# Aktivfilter.net
KiCad netlist of a schematic drawn in EAGLE
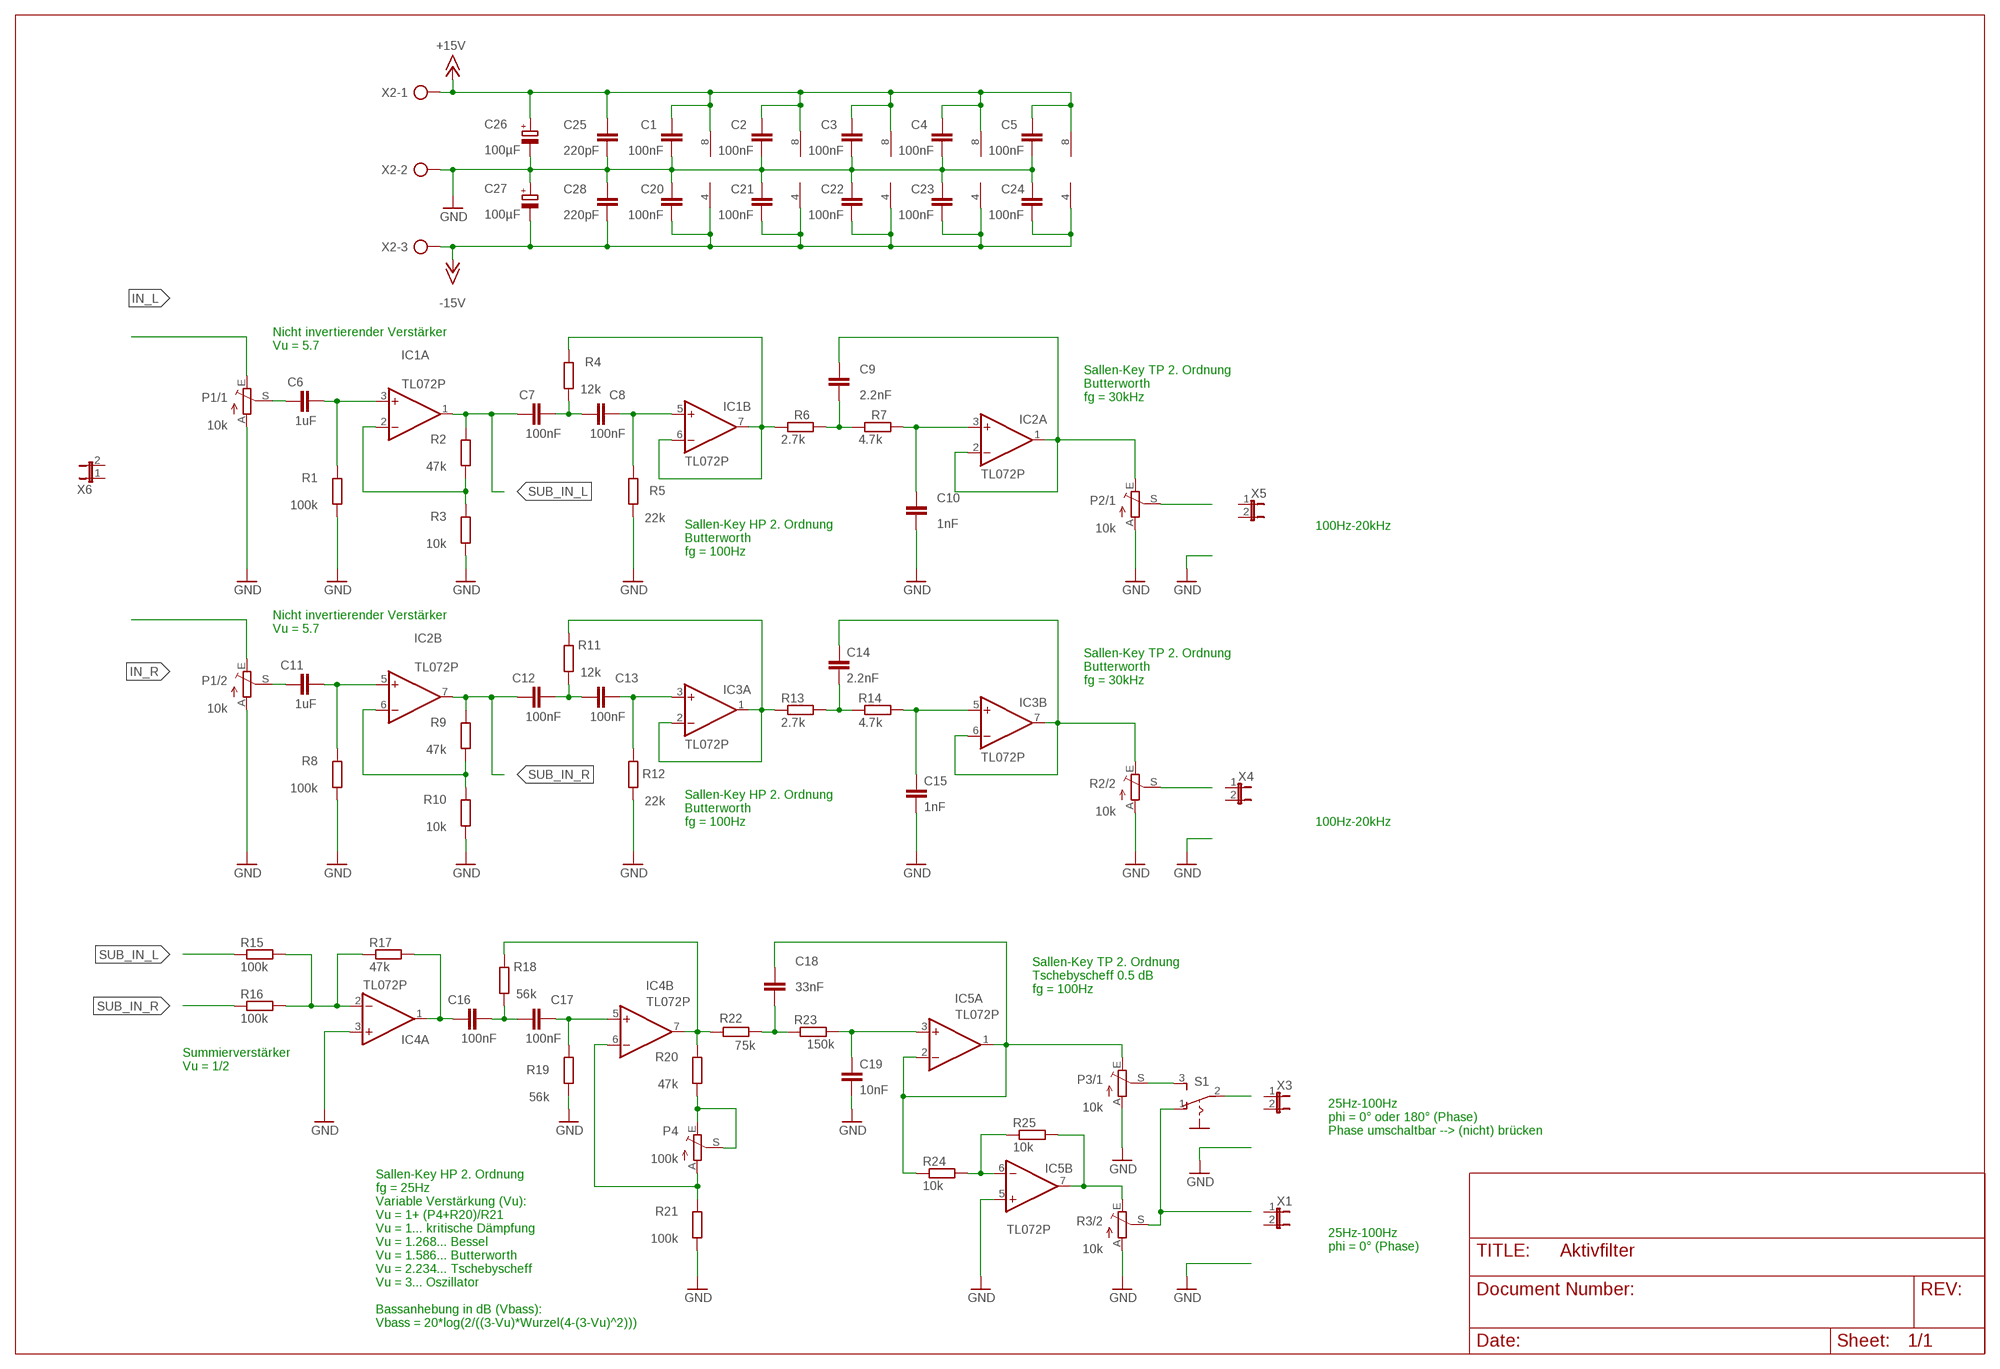
[diagram p0: schematic, sheet 1]

(export (version "E")
  (design (tool "Eeschema 10.0.6"))
  (components
    (comp (ref "C1")
      (value "100nF")
      (footprint "eagle-import:C025-025X050")
      (libsource (lib "eagle-import") (part "C-EU025-025X050"))
    )
    (comp (ref "C2")
      (value "100nF")
      (footprint "eagle-import:C025-025X050")
      (libsource (lib "eagle-import") (part "C-EU025-025X050"))
    )
    (comp (ref "C3")
      (value "100nF")
      (footprint "eagle-import:C025-025X050")
      (libsource (lib "eagle-import") (part "C-EU025-025X050"))
    )
    (comp (ref "C4")
      (value "100nF")
      (footprint "eagle-import:C025-025X050")
      (libsource (lib "eagle-import") (part "C-EU025-025X050"))
    )
    (comp (ref "C5")
      (value "100nF")
      (footprint "eagle-import:C025-025X050")
      (libsource (lib "eagle-import") (part "C-EU025-025X050"))
    )
    (comp (ref "C6")
      (value "1uF")
      (footprint "eagle-import:C025-025X050")
      (libsource (lib "eagle-import") (part "resistor_C-EU025-025X050"))
    )
    (comp (ref "C7")
      (value "100nF")
      (footprint "eagle-import:C025-025X050")
      (libsource (lib "eagle-import") (part "resistor_C-EU025-025X050"))
    )
    (comp (ref "C8")
      (value "100nF")
      (footprint "eagle-import:C025-025X050")
      (libsource (lib "eagle-import") (part "resistor_C-EU025-025X050"))
    )
    (comp (ref "C9")
      (value "2.2nF")
      (footprint "eagle-import:C025-025X050")
      (libsource (lib "eagle-import") (part "resistor_C-EU025-025X050"))
    )
    (comp (ref "C10")
      (value "1nF")
      (footprint "eagle-import:C025-025X050")
      (libsource (lib "eagle-import") (part "resistor_C-EU025-025X050"))
    )
    (comp (ref "C11")
      (value "1uF")
      (footprint "eagle-import:C025-025X050")
      (libsource (lib "eagle-import") (part "resistor_C-EU025-025X050"))
    )
    (comp (ref "C12")
      (value "100nF")
      (footprint "eagle-import:C025-025X050")
      (libsource (lib "eagle-import") (part "resistor_C-EU025-025X050"))
    )
    (comp (ref "C13")
      (value "100nF")
      (footprint "eagle-import:C025-025X050")
      (libsource (lib "eagle-import") (part "resistor_C-EU025-025X050"))
    )
    (comp (ref "C14")
      (value "2.2nF")
      (footprint "eagle-import:C025-025X050")
      (libsource (lib "eagle-import") (part "resistor_C-EU025-025X050"))
    )
    (comp (ref "C15")
      (value "1nF")
      (footprint "eagle-import:C025-025X050")
      (libsource (lib "eagle-import") (part "resistor_C-EU025-025X050"))
    )
    (comp (ref "C16")
      (value "100nF")
      (footprint "eagle-import:C050-025X075")
      (libsource (lib "eagle-import") (part "C-EU050-025X075"))
    )
    (comp (ref "C17")
      (value "100nF")
      (footprint "eagle-import:C025-025X050")
      (libsource (lib "eagle-import") (part "C-EU025-025X050"))
    )
    (comp (ref "C18")
      (value "33nF")
      (footprint "eagle-import:C025-025X050")
      (libsource (lib "eagle-import") (part "C-EU025-025X050"))
    )
    (comp (ref "C19")
      (value "10nF")
      (footprint "eagle-import:C025-025X050")
      (libsource (lib "eagle-import") (part "C-EU025-025X050"))
    )
    (comp (ref "C20")
      (value "100nF")
      (footprint "eagle-import:C025-025X050")
      (libsource (lib "eagle-import") (part "C-EU025-025X050"))
    )
    (comp (ref "C21")
      (value "100nF")
      (footprint "eagle-import:C025-025X050")
      (libsource (lib "eagle-import") (part "C-EU025-025X050"))
    )
    (comp (ref "C22")
      (value "100nF")
      (footprint "eagle-import:C025-025X050")
      (libsource (lib "eagle-import") (part "C-EU025-025X050"))
    )
    (comp (ref "C23")
      (value "100nF")
      (footprint "eagle-import:C025-025X050")
      (libsource (lib "eagle-import") (part "C-EU025-025X050"))
    )
    (comp (ref "C24")
      (value "100nF")
      (footprint "eagle-import:C025-025X050")
      (libsource (lib "eagle-import") (part "C-EU025-025X050"))
    )
    (comp (ref "C25")
      (value "220pF")
      (footprint "eagle-import:C025-025X050")
      (libsource (lib "eagle-import") (part "C-EU025-025X050"))
    )
    (comp (ref "C26")
      (value "100µF")
      (footprint "eagle-import:E2,5-6")
      (libsource (lib "eagle-import") (part "CPOL-EUE2.5-6"))
    )
    (comp (ref "C27")
      (value "100µF")
      (footprint "eagle-import:E2,5-6")
      (libsource (lib "eagle-import") (part "CPOL-EUE2.5-6"))
    )
    (comp (ref "C28")
      (value "220pF")
      (footprint "eagle-import:C025-025X050")
      (libsource (lib "eagle-import") (part "C-EU025-025X050"))
    )
    (comp (ref "IC1")
      (value "TL072P")
      (footprint "eagle-import:DIL08")
      (libsource (lib "eagle-import") (part "TL072P"))
    )
    (comp (ref "IC2")
      (value "TL072P")
      (footprint "eagle-import:DIL08")
      (libsource (lib "eagle-import") (part "TL072P"))
    )
    (comp (ref "IC3")
      (value "TL072P")
      (footprint "eagle-import:DIL08")
      (libsource (lib "eagle-import") (part "TL072P"))
    )
    (comp (ref "IC4")
      (value "TL072P")
      (footprint "eagle-import:DIL08")
      (libsource (lib "eagle-import") (part "TL072P"))
    )
    (comp (ref "IC5")
      (value "TL072P")
      (footprint "eagle-import:DIL08")
      (libsource (lib "eagle-import") (part "TL072P"))
    )
    (comp (ref "P1/1")
      (value "10k")
      (footprint "eagle-import:B64Y")
      (libsource (lib "eagle-import") (part "TRIM_EU-B64Y"))
    )
    (comp (ref "P1/2")
      (value "10k")
      (footprint "eagle-import:B64Y")
      (libsource (lib "eagle-import") (part "TRIM_EU-B64Y"))
    )
    (comp (ref "P2/1")
      (value "10k")
      (footprint "eagle-import:B64Y")
      (libsource (lib "eagle-import") (part "TRIM_EU-B64Y"))
    )
    (comp (ref "P3/1")
      (value "10k")
      (footprint "eagle-import:B64Y")
      (libsource (lib "eagle-import") (part "TRIM_EU-B64Y"))
    )
    (comp (ref "P4")
      (value "100k")
      (footprint "eagle-import:B64Y")
      (libsource (lib "eagle-import") (part "TRIM_EU-B64Y"))
    )
    (comp (ref "R1")
      (value "100k")
      (footprint "eagle-import:0207_10")
      (libsource (lib "eagle-import") (part "resistor_R-EU_0207/10"))
    )
    (comp (ref "R2")
      (value "47k")
      (footprint "eagle-import:0207_10")
      (libsource (lib "eagle-import") (part "resistor_R-EU_0207/10"))
    )
    (comp (ref "R2/2")
      (value "10k")
      (footprint "eagle-import:B64Y")
      (libsource (lib "eagle-import") (part "TRIM_EU-B64Y"))
    )
    (comp (ref "R3")
      (value "10k")
      (footprint "eagle-import:0207_10")
      (libsource (lib "eagle-import") (part "resistor_R-EU_0207/10"))
    )
    (comp (ref "R3/2")
      (value "10k")
      (footprint "eagle-import:B64Y")
      (libsource (lib "eagle-import") (part "TRIM_EU-B64Y"))
    )
    (comp (ref "R4")
      (value "12k")
      (footprint "eagle-import:0207_10")
      (libsource (lib "eagle-import") (part "resistor_R-EU_0207/10"))
    )
    (comp (ref "R5")
      (value "22k")
      (footprint "eagle-import:0207_10")
      (libsource (lib "eagle-import") (part "resistor_R-EU_0207/10"))
    )
    (comp (ref "R6")
      (value "2.7k")
      (footprint "eagle-import:0207_10")
      (libsource (lib "eagle-import") (part "resistor_R-EU_0207/10"))
    )
    (comp (ref "R7")
      (value "4.7k")
      (footprint "eagle-import:0207_10")
      (libsource (lib "eagle-import") (part "resistor_R-EU_0207/10"))
    )
    (comp (ref "R8")
      (value "100k")
      (footprint "eagle-import:0207_7")
      (libsource (lib "eagle-import") (part "R-EU_0207/7"))
    )
    (comp (ref "R9")
      (value "47k")
      (footprint "eagle-import:0207_7")
      (libsource (lib "eagle-import") (part "R-EU_0207/7"))
    )
    (comp (ref "R10")
      (value "10k")
      (footprint "eagle-import:0207_10")
      (libsource (lib "eagle-import") (part "resistor_R-EU_0207/10"))
    )
    (comp (ref "R11")
      (value "12k")
      (footprint "eagle-import:0207_10")
      (libsource (lib "eagle-import") (part "resistor_R-EU_0207/10"))
    )
    (comp (ref "R12")
      (value "22k")
      (footprint "eagle-import:0207_10")
      (libsource (lib "eagle-import") (part "resistor_R-EU_0207/10"))
    )
    (comp (ref "R13")
      (value "2.7k")
      (footprint "eagle-import:0207_10")
      (libsource (lib "eagle-import") (part "resistor_R-EU_0207/10"))
    )
    (comp (ref "R14")
      (value "4.7k")
      (footprint "eagle-import:0207_10")
      (libsource (lib "eagle-import") (part "resistor_R-EU_0207/10"))
    )
    (comp (ref "R15")
      (value "100k")
      (footprint "eagle-import:0207_10")
      (libsource (lib "eagle-import") (part "R-EU_0207/10"))
    )
    (comp (ref "R16")
      (value "100k")
      (footprint "eagle-import:0207_10")
      (libsource (lib "eagle-import") (part "R-EU_0207/10"))
    )
    (comp (ref "R17")
      (value "47k")
      (footprint "eagle-import:0207_10")
      (libsource (lib "eagle-import") (part "R-EU_0207/10"))
    )
    (comp (ref "R18")
      (value "56k")
      (footprint "eagle-import:0207_10")
      (libsource (lib "eagle-import") (part "R-EU_0207/10"))
    )
    (comp (ref "R19")
      (value "56k")
      (footprint "eagle-import:0207_7")
      (libsource (lib "eagle-import") (part "R-EU_0207/7"))
    )
    (comp (ref "R20")
      (value "47k")
      (footprint "eagle-import:0207_10")
      (libsource (lib "eagle-import") (part "R-EU_0207/10"))
    )
    (comp (ref "R21")
      (value "100k")
      (footprint "eagle-import:0207_10")
      (libsource (lib "eagle-import") (part "R-EU_0207/10"))
    )
    (comp (ref "R22")
      (value "75k")
      (footprint "eagle-import:0207_7")
      (libsource (lib "eagle-import") (part "R-EU_0207/7"))
    )
    (comp (ref "R23")
      (value "150k")
      (footprint "eagle-import:0207_10")
      (libsource (lib "eagle-import") (part "R-EU_0207/10"))
    )
    (comp (ref "R24")
      (value "10k")
      (footprint "eagle-import:0207_10")
      (libsource (lib "eagle-import") (part "R-EU_0207/10"))
    )
    (comp (ref "R25")
      (value "10k")
      (footprint "eagle-import:0207_10")
      (libsource (lib "eagle-import") (part "R-EU_0207/10"))
    )
    (comp (ref "S1")
      (value "255SB")
      (footprint "eagle-import:255SB")
      (libsource (lib "eagle-import") (part "255SB"))
    )
    (comp (ref "X1")
      (value "JMP2")
      (footprint "eagle-import:JMP2")
      (libsource (lib "eagle-import") (part "JMP2"))
    )
    (comp (ref "X2")
      (value "AK300/3")
      (footprint "eagle-import:AK300_3")
      (libsource (lib "eagle-import") (part "AK300/3"))
    )
    (comp (ref "X3")
      (value "JMP2")
      (footprint "eagle-import:JMP2")
      (libsource (lib "eagle-import") (part "JMP2"))
    )
    (comp (ref "X4")
      (value "JMP2")
      (footprint "eagle-import:JMP2")
      (libsource (lib "eagle-import") (part "JMP2"))
    )
    (comp (ref "X5")
      (value "JMP2")
      (footprint "eagle-import:JMP2")
      (libsource (lib "eagle-import") (part "JMP2"))
    )
    (comp (ref "X6")
      (value "JMP2")
      (footprint "eagle-import:JMP2")
      (libsource (lib "eagle-import") (part "JMP2"))
    )
  )
  (nets
    (net (code "1") (name "+15V") (class "Default")
      (node (ref "C1") (pin "1") (pinfunction "1_1") (pintype "passive"))
      (node (ref "C2") (pin "1") (pinfunction "1_1") (pintype "passive"))
      (node (ref "C25") (pin "1") (pinfunction "1_1") (pintype "passive"))
      (node (ref "C26") (pin "+") (pinfunction "+_+") (pintype "passive"))
      (node (ref "C3") (pin "1") (pinfunction "1_1") (pintype "passive"))
      (node (ref "C4") (pin "1") (pinfunction "1_1") (pintype "passive"))
      (node (ref "C5") (pin "1") (pinfunction "1_1") (pintype "passive"))
      (node (ref "IC1") (pin "8") (pinfunction "V+_8") (pintype "power_in"))
      (node (ref "IC2") (pin "8") (pinfunction "V+_8") (pintype "power_in"))
      (node (ref "IC3") (pin "8") (pinfunction "V+_8") (pintype "power_in"))
      (node (ref "IC4") (pin "8") (pinfunction "V+_8") (pintype "power_in"))
      (node (ref "IC5") (pin "8") (pinfunction "V+_8") (pintype "power_in"))
      (node (ref "X2") (pin "1") (pinfunction "KL_1") (pintype "passive"))
    )
    (net (code "2") (name "-15V") (class "Default")
      (node (ref "C20") (pin "2") (pinfunction "2_2") (pintype "passive"))
      (node (ref "C21") (pin "2") (pinfunction "2_2") (pintype "passive"))
      (node (ref "C22") (pin "2") (pinfunction "2_2") (pintype "passive"))
      (node (ref "C23") (pin "2") (pinfunction "2_2") (pintype "passive"))
      (node (ref "C24") (pin "2") (pinfunction "2_2") (pintype "passive"))
      (node (ref "C27") (pin "-") (pinfunction "-_-") (pintype "passive"))
      (node (ref "C28") (pin "2") (pinfunction "2_2") (pintype "passive"))
      (node (ref "IC1") (pin "4") (pinfunction "V-_4") (pintype "power_in"))
      (node (ref "IC2") (pin "4") (pinfunction "V-_4") (pintype "power_in"))
      (node (ref "IC3") (pin "4") (pinfunction "V-_4") (pintype "power_in"))
      (node (ref "IC4") (pin "4") (pinfunction "V-_4") (pintype "power_in"))
      (node (ref "IC5") (pin "4") (pinfunction "V-_4") (pintype "power_in"))
      (node (ref "X2") (pin "3") (pinfunction "KL_3") (pintype "passive"))
    )
    (net (code "3") (name "GND") (class "Default")
      (node (ref "C1") (pin "2") (pinfunction "2_2") (pintype "passive"))
      (node (ref "C10") (pin "2") (pinfunction "2_2") (pintype "passive"))
      (node (ref "C15") (pin "2") (pinfunction "2_2") (pintype "passive"))
      (node (ref "C19") (pin "2") (pinfunction "2_2") (pintype "passive"))
      (node (ref "C2") (pin "2") (pinfunction "2_2") (pintype "passive"))
      (node (ref "C20") (pin "1") (pinfunction "1_1") (pintype "passive"))
      (node (ref "C21") (pin "1") (pinfunction "1_1") (pintype "passive"))
      (node (ref "C22") (pin "1") (pinfunction "1_1") (pintype "passive"))
      (node (ref "C23") (pin "1") (pinfunction "1_1") (pintype "passive"))
      (node (ref "C24") (pin "1") (pinfunction "1_1") (pintype "passive"))
      (node (ref "C25") (pin "2") (pinfunction "2_2") (pintype "passive"))
      (node (ref "C26") (pin "-") (pinfunction "-_-") (pintype "passive"))
      (node (ref "C27") (pin "+") (pinfunction "+_+") (pintype "passive"))
      (node (ref "C28") (pin "1") (pinfunction "1_1") (pintype "passive"))
      (node (ref "C3") (pin "2") (pinfunction "2_2") (pintype "passive"))
      (node (ref "C4") (pin "2") (pinfunction "2_2") (pintype "passive"))
      (node (ref "C5") (pin "2") (pinfunction "2_2") (pintype "passive"))
      (node (ref "IC4") (pin "3") (pinfunction "+IN_3") (pintype "input"))
      (node (ref "IC5") (pin "5") (pinfunction "+IN_5") (pintype "input"))
      (node (ref "P1/1") (pin "A") (pinfunction "A_A") (pintype "passive"))
      (node (ref "P1/2") (pin "A") (pinfunction "A_A") (pintype "passive"))
      (node (ref "P2/1") (pin "A") (pinfunction "A_A") (pintype "passive"))
      (node (ref "P3/1") (pin "A") (pinfunction "A_A") (pintype "passive"))
      (node (ref "R1") (pin "1") (pinfunction "1_1") (pintype "passive"))
      (node (ref "R10") (pin "1") (pinfunction "1_1") (pintype "passive"))
      (node (ref "R12") (pin "1") (pinfunction "1_1") (pintype "passive"))
      (node (ref "R19") (pin "1") (pinfunction "1_1") (pintype "passive"))
      (node (ref "R2/2") (pin "A") (pinfunction "A_A") (pintype "passive"))
      (node (ref "R21") (pin "1") (pinfunction "1_1") (pintype "passive"))
      (node (ref "R3") (pin "1") (pinfunction "1_1") (pintype "passive"))
      (node (ref "R3/2") (pin "A") (pinfunction "A_A") (pintype "passive"))
      (node (ref "R5") (pin "1") (pinfunction "1_1") (pintype "passive"))
      (node (ref "R8") (pin "1") (pinfunction "1_1") (pintype "passive"))
      (node (ref "X2") (pin "2") (pinfunction "KL_2") (pintype "passive"))
    )
    (net (code "4") (name "IN_L") (class "Default")
      (node (ref "P1/1") (pin "E") (pinfunction "E_E") (pintype "passive"))
    )
    (net (code "5") (name "IN_R") (class "Default")
      (node (ref "P1/2") (pin "E") (pinfunction "E_E") (pintype "passive"))
    )
    (net (code "6") (name "Net-(C6-Pad1)") (class "Default")
      (node (ref "C6") (pin "1") (pinfunction "1_1") (pintype "passive"))
      (node (ref "P1/1") (pin "S") (pinfunction "S_S") (pintype "passive"))
    )
    (net (code "7") (name "Net-(C7-Pad2)") (class "Default")
      (node (ref "C7") (pin "2") (pinfunction "2_2") (pintype "passive"))
      (node (ref "C8") (pin "1") (pinfunction "1_1") (pintype "passive"))
      (node (ref "R4") (pin "1") (pinfunction "1_1") (pintype "passive"))
    )
    (net (code "8") (name "Net-(C9-Pad2)") (class "Default")
      (node (ref "C9") (pin "2") (pinfunction "2_2") (pintype "passive"))
      (node (ref "R6") (pin "2") (pinfunction "2_2") (pintype "passive"))
      (node (ref "R7") (pin "1") (pinfunction "1_1") (pintype "passive"))
    )
    (net (code "9") (name "Net-(C11-Pad1)") (class "Default")
      (node (ref "C11") (pin "1") (pinfunction "1_1") (pintype "passive"))
      (node (ref "P1/2") (pin "S") (pinfunction "S_S") (pintype "passive"))
    )
    (net (code "10") (name "Net-(C12-Pad2)") (class "Default")
      (node (ref "C12") (pin "2") (pinfunction "2_2") (pintype "passive"))
      (node (ref "C13") (pin "1") (pinfunction "1_1") (pintype "passive"))
      (node (ref "R11") (pin "1") (pinfunction "1_1") (pintype "passive"))
    )
    (net (code "11") (name "Net-(C14-Pad2)") (class "Default")
      (node (ref "C14") (pin "2") (pinfunction "2_2") (pintype "passive"))
      (node (ref "R13") (pin "2") (pinfunction "2_2") (pintype "passive"))
      (node (ref "R14") (pin "1") (pinfunction "1_1") (pintype "passive"))
    )
    (net (code "12") (name "Net-(C16-Pad2)") (class "Default")
      (node (ref "C16") (pin "2") (pinfunction "2_2") (pintype "passive"))
      (node (ref "C17") (pin "1") (pinfunction "1_1") (pintype "passive"))
      (node (ref "R18") (pin "1") (pinfunction "1_1") (pintype "passive"))
    )
    (net (code "13") (name "Net-(C18-Pad2)") (class "Default")
      (node (ref "C18") (pin "2") (pinfunction "2_2") (pintype "passive"))
      (node (ref "R22") (pin "1") (pinfunction "1_1") (pintype "passive"))
      (node (ref "R23") (pin "1") (pinfunction "1_1") (pintype "passive"))
    )
    (net (code "14") (name "Net-(IC1A-+IN)") (class "Default")
      (node (ref "C6") (pin "2") (pinfunction "2_2") (pintype "passive"))
      (node (ref "IC1") (pin "3") (pinfunction "+IN_3") (pintype "input"))
      (node (ref "R1") (pin "2") (pinfunction "2_2") (pintype "passive"))
    )
    (net (code "15") (name "Net-(IC1A--IN)") (class "Default")
      (node (ref "IC1") (pin "2") (pinfunction "-IN_2") (pintype "input"))
      (node (ref "R2") (pin "1") (pinfunction "1_1") (pintype "passive"))
      (node (ref "R3") (pin "2") (pinfunction "2_2") (pintype "passive"))
    )
    (net (code "16") (name "Net-(IC1B-+IN)") (class "Default")
      (node (ref "C8") (pin "2") (pinfunction "2_2") (pintype "passive"))
      (node (ref "IC1") (pin "5") (pinfunction "+IN_5") (pintype "input"))
      (node (ref "R5") (pin "2") (pinfunction "2_2") (pintype "passive"))
    )
    (net (code "17") (name "Net-(IC1B--IN)") (class "Default")
      (node (ref "IC1") (pin "6") (pinfunction "-IN_6") (pintype "input"))
      (node (ref "IC1") (pin "7") (pinfunction "OUT_7") (pintype "output"))
      (node (ref "R4") (pin "2") (pinfunction "2_2") (pintype "passive"))
      (node (ref "R6") (pin "1") (pinfunction "1_1") (pintype "passive"))
    )
    (net (code "18") (name "Net-(IC2A-+IN)") (class "Default")
      (node (ref "C10") (pin "1") (pinfunction "1_1") (pintype "passive"))
      (node (ref "IC2") (pin "3") (pinfunction "+IN_3") (pintype "input"))
      (node (ref "R7") (pin "2") (pinfunction "2_2") (pintype "passive"))
    )
    (net (code "19") (name "Net-(IC2A--IN)") (class "Default")
      (node (ref "C9") (pin "1") (pinfunction "1_1") (pintype "passive"))
      (node (ref "IC2") (pin "1") (pinfunction "OUT_1") (pintype "output"))
      (node (ref "IC2") (pin "2") (pinfunction "-IN_2") (pintype "input"))
      (node (ref "P2/1") (pin "E") (pinfunction "E_E") (pintype "passive"))
    )
    (net (code "20") (name "Net-(IC2B-+IN)") (class "Default")
      (node (ref "C11") (pin "2") (pinfunction "2_2") (pintype "passive"))
      (node (ref "IC2") (pin "5") (pinfunction "+IN_5") (pintype "input"))
      (node (ref "R8") (pin "2") (pinfunction "2_2") (pintype "passive"))
    )
    (net (code "21") (name "Net-(IC2B--IN)") (class "Default")
      (node (ref "IC2") (pin "6") (pinfunction "-IN_6") (pintype "input"))
      (node (ref "R10") (pin "2") (pinfunction "2_2") (pintype "passive"))
      (node (ref "R9") (pin "1") (pinfunction "1_1") (pintype "passive"))
    )
    (net (code "22") (name "Net-(IC3A-+IN)") (class "Default")
      (node (ref "C13") (pin "2") (pinfunction "2_2") (pintype "passive"))
      (node (ref "IC3") (pin "3") (pinfunction "+IN_3") (pintype "input"))
      (node (ref "R12") (pin "2") (pinfunction "2_2") (pintype "passive"))
    )
    (net (code "23") (name "Net-(IC3A--IN)") (class "Default")
      (node (ref "IC3") (pin "1") (pinfunction "OUT_1") (pintype "output"))
      (node (ref "IC3") (pin "2") (pinfunction "-IN_2") (pintype "input"))
      (node (ref "R11") (pin "2") (pinfunction "2_2") (pintype "passive"))
      (node (ref "R13") (pin "1") (pinfunction "1_1") (pintype "passive"))
    )
    (net (code "24") (name "Net-(IC3B-+IN)") (class "Default")
      (node (ref "C15") (pin "1") (pinfunction "1_1") (pintype "passive"))
      (node (ref "IC3") (pin "5") (pinfunction "+IN_5") (pintype "input"))
      (node (ref "R14") (pin "2") (pinfunction "2_2") (pintype "passive"))
    )
    (net (code "25") (name "Net-(IC3B--IN)") (class "Default")
      (node (ref "C14") (pin "1") (pinfunction "1_1") (pintype "passive"))
      (node (ref "IC3") (pin "6") (pinfunction "-IN_6") (pintype "input"))
      (node (ref "IC3") (pin "7") (pinfunction "OUT_7") (pintype "output"))
      (node (ref "R2/2") (pin "E") (pinfunction "E_E") (pintype "passive"))
    )
    (net (code "26") (name "Net-(IC4A--IN)") (class "Default")
      (node (ref "IC4") (pin "2") (pinfunction "-IN_2") (pintype "input"))
      (node (ref "R15") (pin "2") (pinfunction "2_2") (pintype "passive"))
      (node (ref "R16") (pin "2") (pinfunction "2_2") (pintype "passive"))
      (node (ref "R17") (pin "1") (pinfunction "1_1") (pintype "passive"))
    )
    (net (code "27") (name "Net-(IC4A-OUT)") (class "Default")
      (node (ref "C16") (pin "1") (pinfunction "1_1") (pintype "passive"))
      (node (ref "IC4") (pin "1") (pinfunction "OUT_1") (pintype "output"))
      (node (ref "R17") (pin "2") (pinfunction "2_2") (pintype "passive"))
    )
    (net (code "28") (name "Net-(IC4B-+IN)") (class "Default")
      (node (ref "C17") (pin "2") (pinfunction "2_2") (pintype "passive"))
      (node (ref "IC4") (pin "5") (pinfunction "+IN_5") (pintype "input"))
      (node (ref "R19") (pin "2") (pinfunction "2_2") (pintype "passive"))
    )
    (net (code "29") (name "Net-(IC4B--IN)") (class "Default")
      (node (ref "IC4") (pin "6") (pinfunction "-IN_6") (pintype "input"))
      (node (ref "P4") (pin "A") (pinfunction "A_A") (pintype "passive"))
      (node (ref "R21") (pin "2") (pinfunction "2_2") (pintype "passive"))
    )
    (net (code "30") (name "Net-(IC4B-OUT)") (class "Default")
      (node (ref "IC4") (pin "7") (pinfunction "OUT_7") (pintype "output"))
      (node (ref "R18") (pin "2") (pinfunction "2_2") (pintype "passive"))
      (node (ref "R20") (pin "2") (pinfunction "2_2") (pintype "passive"))
      (node (ref "R22") (pin "2") (pinfunction "2_2") (pintype "passive"))
    )
    (net (code "31") (name "Net-(IC5A-+IN)") (class "Default")
      (node (ref "C19") (pin "1") (pinfunction "1_1") (pintype "passive"))
      (node (ref "IC5") (pin "3") (pinfunction "+IN_3") (pintype "input"))
      (node (ref "R23") (pin "2") (pinfunction "2_2") (pintype "passive"))
    )
    (net (code "32") (name "Net-(IC5A--IN)") (class "Default")
      (node (ref "C18") (pin "1") (pinfunction "1_1") (pintype "passive"))
      (node (ref "IC5") (pin "1") (pinfunction "OUT_1") (pintype "output"))
      (node (ref "IC5") (pin "2") (pinfunction "-IN_2") (pintype "input"))
      (node (ref "P3/1") (pin "E") (pinfunction "E_E") (pintype "passive"))
      (node (ref "R24") (pin "1") (pinfunction "1_1") (pintype "passive"))
    )
    (net (code "33") (name "Net-(IC5B--IN)") (class "Default")
      (node (ref "IC5") (pin "6") (pinfunction "-IN_6") (pintype "input"))
      (node (ref "R24") (pin "2") (pinfunction "2_2") (pintype "passive"))
      (node (ref "R25") (pin "1") (pinfunction "1_1") (pintype "passive"))
    )
    (net (code "34") (name "Net-(IC5B-OUT)") (class "Default")
      (node (ref "IC5") (pin "7") (pinfunction "OUT_7") (pintype "output"))
      (node (ref "R25") (pin "2") (pinfunction "2_2") (pintype "passive"))
      (node (ref "R3/2") (pin "E") (pinfunction "E_E") (pintype "passive"))
    )
    (net (code "35") (name "Net-(P4-PadE)") (class "Default")
      (node (ref "P4") (pin "E") (pinfunction "E_E") (pintype "passive"))
      (node (ref "P4") (pin "S") (pinfunction "S_S") (pintype "passive"))
      (node (ref "R20") (pin "1") (pinfunction "1_1") (pintype "passive"))
    )
    (net (code "36") (name "Net-(S1-O)") (class "Default")
      (node (ref "R3/2") (pin "S") (pinfunction "S_S") (pintype "passive"))
      (node (ref "S1") (pin "1") (pinfunction "O_1") (pintype "passive"))
    )
    (net (code "37") (name "Net-(S1-S)") (class "Default")
      (node (ref "P3/1") (pin "S") (pinfunction "S_S") (pintype "passive"))
      (node (ref "S1") (pin "3") (pinfunction "S_3") (pintype "passive"))
    )
    (net (code "38") (name "SUB_IN_L") (class "Default")
      (node (ref "C7") (pin "1") (pinfunction "1_1") (pintype "passive"))
      (node (ref "IC1") (pin "1") (pinfunction "OUT_1") (pintype "output"))
      (node (ref "R15") (pin "1") (pinfunction "1_1") (pintype "passive"))
      (node (ref "R2") (pin "2") (pinfunction "2_2") (pintype "passive"))
    )
    (net (code "39") (name "SUB_IN_R") (class "Default")
      (node (ref "C12") (pin "1") (pinfunction "1_1") (pintype "passive"))
      (node (ref "IC2") (pin "7") (pinfunction "OUT_7") (pintype "output"))
      (node (ref "R16") (pin "1") (pinfunction "1_1") (pintype "passive"))
      (node (ref "R9") (pin "2") (pinfunction "2_2") (pintype "passive"))
    )
    (net (code "40") (name "unconnected-(P2/1-PadS)") (class "Default")
      (node (ref "P2/1") (pin "S") (pinfunction "S_S") (pintype "passive"))
    )
    (net (code "41") (name "unconnected-(R2/2-PadS)") (class "Default")
      (node (ref "R2/2") (pin "S") (pinfunction "S_S") (pintype "passive"))
    )
    (net (code "42") (name "unconnected-(S1-P-Pad2)") (class "Default")
      (node (ref "S1") (pin "2") (pinfunction "P_2") (pintype "passive"))
    )
    (net (code "43") (name "unconnected-(X1-Pad1)") (class "Default")
      (node (ref "X1") (pin "1") (pinfunction "1_1") (pintype "passive"))
    )
    (net (code "44") (name "unconnected-(X1-Pad2)") (class "Default")
      (node (ref "X1") (pin "2") (pinfunction "2_2") (pintype "passive"))
    )
    (net (code "45") (name "unconnected-(X3-Pad1)") (class "Default")
      (node (ref "X3") (pin "1") (pinfunction "1_1") (pintype "passive"))
    )
    (net (code "46") (name "unconnected-(X3-Pad2)") (class "Default")
      (node (ref "X3") (pin "2") (pinfunction "2_2") (pintype "passive"))
    )
    (net (code "47") (name "unconnected-(X4-Pad1)") (class "Default")
      (node (ref "X4") (pin "1") (pinfunction "1_1") (pintype "passive"))
    )
    (net (code "48") (name "unconnected-(X4-Pad2)") (class "Default")
      (node (ref "X4") (pin "2") (pinfunction "2_2") (pintype "passive"))
    )
    (net (code "49") (name "unconnected-(X5-Pad1)") (class "Default")
      (node (ref "X5") (pin "1") (pinfunction "1_1") (pintype "passive"))
    )
    (net (code "50") (name "unconnected-(X5-Pad2)") (class "Default")
      (node (ref "X5") (pin "2") (pinfunction "2_2") (pintype "passive"))
    )
    (net (code "51") (name "unconnected-(X6-Pad1)") (class "Default")
      (node (ref "X6") (pin "1") (pinfunction "1_1") (pintype "passive"))
    )
    (net (code "52") (name "unconnected-(X6-Pad2)") (class "Default")
      (node (ref "X6") (pin "2") (pinfunction "2_2") (pintype "passive"))
    )
  )
)
